# PSU.net
KiCad netlist of a schematic drawn in Altium Designer
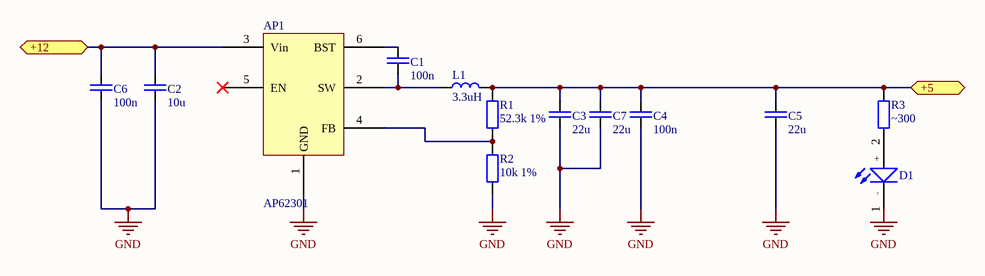
[diagram p0: PSU.SchDoc]

(export (version "E")
  (design (tool "Eeschema 10.0.6"))
  (components
    (comp (ref "AP1")
      (value "AP62301")
      (footprint "SOT95P280X100-6L")
      (libsource (lib "PiVO") (part "AP62301"))
    )
    (comp (ref "C1")
      (value "100n")
      (footprint "C3216_1206I_L")
      (description "Capacitor")
      (libsource (lib "General") (part "C"))
    )
    (comp (ref "C2")
      (value "10u")
      (footprint "C3225_1210I_L")
      (description "Capacitor")
      (libsource (lib "General") (part "C"))
    )
    (comp (ref "C3")
      (value "22u")
      (footprint "C3225_1210I_L")
      (description "Capacitor")
      (libsource (lib "General") (part "C"))
    )
    (comp (ref "C4")
      (value "100n")
      (footprint "C3216_1206I_L")
      (description "Capacitor")
      (libsource (lib "General") (part "C"))
    )
    (comp (ref "C5")
      (value "22u")
      (footprint "C3225_1210I_L")
      (description "Capacitor")
      (libsource (lib "General") (part "C"))
    )
    (comp (ref "C6")
      (value "100n")
      (footprint "C3216_1206I_L")
      (description "Capacitor")
      (libsource (lib "General") (part "C"))
    )
    (comp (ref "C7")
      (value "22u")
      (footprint "C3225_1210I_L")
      (description "Capacitor")
      (libsource (lib "General") (part "C"))
    )
    (comp (ref "D1") (value "LED") (footprint "LED1608_0603I_L") (libsource (lib "General") (part "LED")))
    (comp (ref "L1")
      (value "3.3uH")
      (footprint "INDUCTOR")
      (description "L")
      (libsource (lib "General") (part "L"))
    )
    (comp (ref "R1")
      (value "52.3k 1%")
      (footprint "R1005_0402i_L")
      (description "R")
      (libsource (lib "General") (part "R"))
    )
    (comp (ref "R2")
      (value "10k 1%")
      (footprint "R1005_0402i_L")
      (description "R")
      (libsource (lib "General") (part "R"))
    )
    (comp (ref "R3")
      (value "~300")
      (footprint "R1005_0402i_L")
      (description "R")
      (libsource (lib "General") (part "R"))
    )
  )
  (nets
    (net (code "1") (name "/+5") (class "Default")
      (node (ref "C3") (pin "1") (pinfunction "1_1") (pintype "passive"))
      (node (ref "C4") (pin "1") (pinfunction "1_1") (pintype "passive"))
      (node (ref "C5") (pin "1") (pinfunction "1_1") (pintype "passive"))
      (node (ref "C7") (pin "1") (pinfunction "1_1") (pintype "passive"))
      (node (ref "L1") (pin "2") (pintype "passive"))
      (node (ref "R1") (pin "1") (pintype "passive"))
      (node (ref "R3") (pin "1") (pintype "passive"))
    )
    (net (code "2") (name "/+12") (class "Default")
      (node (ref "AP1") (pin "3") (pinfunction "Vin_3") (pintype "passive"))
      (node (ref "C2") (pin "1") (pinfunction "1_1") (pintype "passive"))
      (node (ref "C6") (pin "1") (pinfunction "1_1") (pintype "passive"))
    )
    (net (code "3") (name "GND") (class "Default")
      (node (ref "AP1") (pin "1") (pinfunction "GND_1") (pintype "passive"))
      (node (ref "C2") (pin "2") (pinfunction "2_2") (pintype "passive"))
      (node (ref "C3") (pin "2") (pinfunction "2_2") (pintype "passive"))
      (node (ref "C4") (pin "2") (pinfunction "2_2") (pintype "passive"))
      (node (ref "C5") (pin "2") (pinfunction "2_2") (pintype "passive"))
      (node (ref "C6") (pin "2") (pinfunction "2_2") (pintype "passive"))
      (node (ref "C7") (pin "2") (pinfunction "2_2") (pintype "passive"))
      (node (ref "D1") (pin "1") (pinfunction "-_1") (pintype "passive"))
      (node (ref "R2") (pin "2") (pintype "passive"))
    )
    (net (code "4") (name "Net-(AP1-BST)") (class "Default")
      (node (ref "AP1") (pin "6") (pinfunction "BST_6") (pintype "passive"))
      (node (ref "C1") (pin "1") (pinfunction "1_1") (pintype "passive"))
    )
    (net (code "5") (name "Net-(AP1-FB)") (class "Default")
      (node (ref "AP1") (pin "4") (pinfunction "FB_4") (pintype "passive"))
      (node (ref "R1") (pin "2") (pintype "passive"))
      (node (ref "R2") (pin "1") (pintype "passive"))
    )
    (net (code "6") (name "Net-(AP1-SW)") (class "Default")
      (node (ref "AP1") (pin "2") (pinfunction "SW_2") (pintype "passive"))
      (node (ref "C1") (pin "2") (pinfunction "2_2") (pintype "passive"))
      (node (ref "L1") (pin "1") (pintype "passive"))
    )
    (net (code "7") (name "Net-(D1-+)") (class "Default")
      (node (ref "D1") (pin "2") (pinfunction "+_2") (pintype "passive"))
      (node (ref "R3") (pin "2") (pintype "passive"))
    )
    (net (code "8") (name "unconnected-(AP1-EN-Pad5)") (class "Default")
      (node (ref "AP1") (pin "5") (pinfunction "EN_5") (pintype "passive+no_connect"))
    )
  )
)
